# Sheet2.net
KiCad netlist of a schematic drawn in Altium Designer
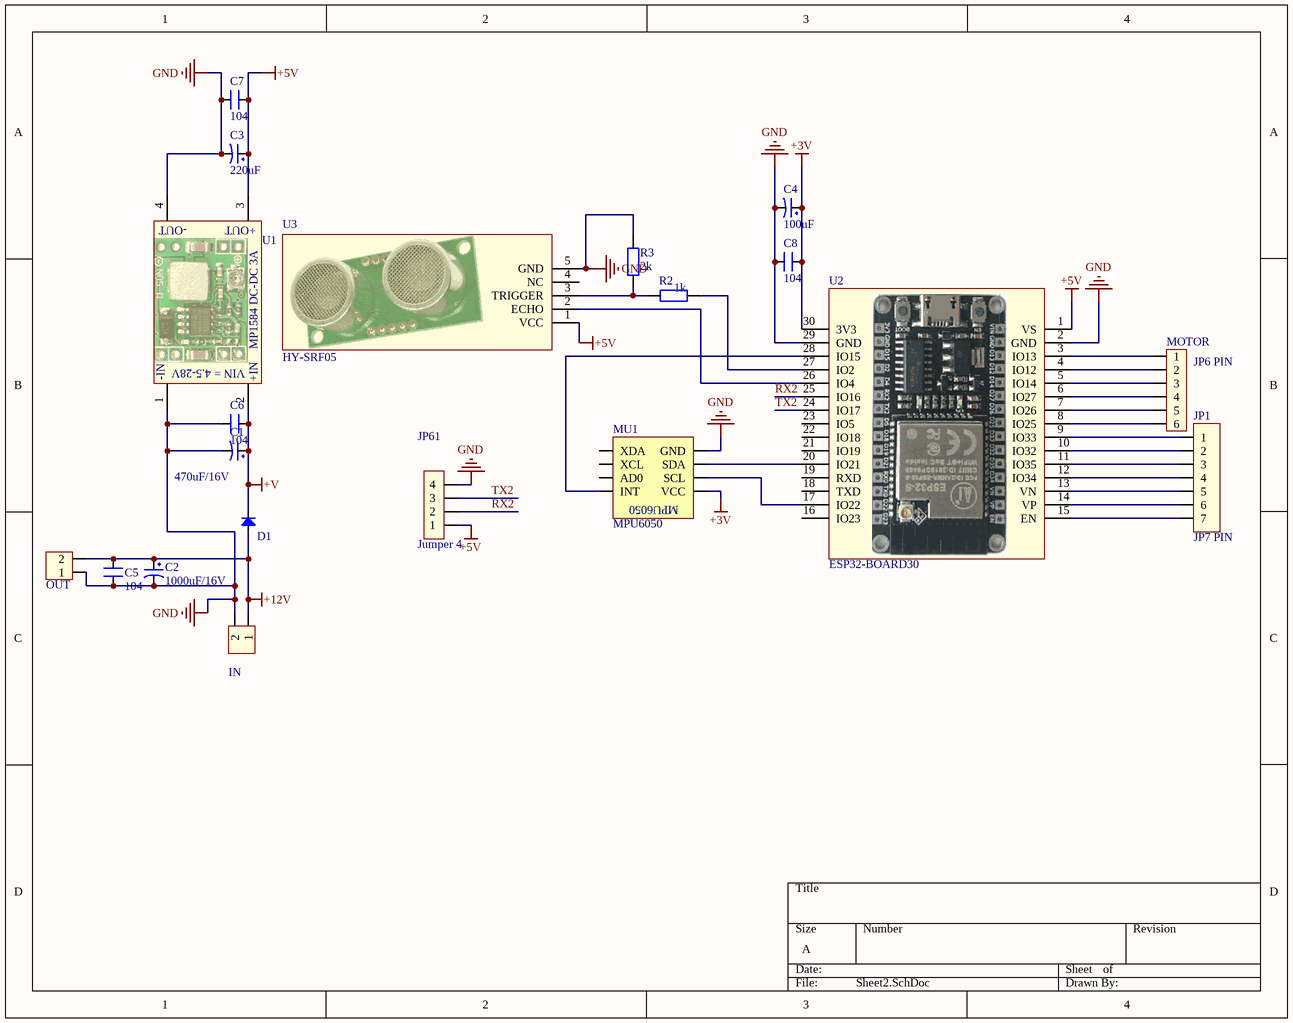
[diagram p0: Sheet2.SchDoc]

(export (version "E")
  (design (tool "Eeschema 10.0.6"))
  (components
    (comp (ref "C1")
      (value "470uF/16V")
      (footprint "CP1.5/3.4")
      (description "Cap 100uF/35V - 470uF/16V")
      (libsource (lib "PART_VDE") (part "CP3"))
    )
    (comp (ref "C2")
      (value "1000uF/16V")
      (footprint "CP1.5/3.4")
      (description "Cap 1000uF/16V - 220uF/50V")
      (libsource (lib "PART_VDE") (part "CP4"))
    )
    (comp (ref "C3")
      (value "220uF")
      (footprint "CP1/2.5")
      (description "C 47uF/50V , 220uF/16V")
      (libsource (lib "PART_VDE") (part "CP2"))
    )
    (comp (ref "C4")
      (value "100uF")
      (footprint "CP1/2")
      (description "Cap P  0,1uF < 22uF , 16 - 50V")
      (libsource (lib "PART_VDE") (part "CP1"))
    )
    (comp (ref "C5")
      (value "104")
      (footprint "CN1.5")
      (description "Cap np 104 => 105pF")
      (libsource (lib "PART_VDE") (part "CN2"))
    )
    (comp (ref "C6")
      (value "104")
      (footprint "CN1.5")
      (description "Cap np 104 => 105pF")
      (libsource (lib "PART_VDE") (part "CN2"))
    )
    (comp (ref "C7")
      (value "104")
      (footprint "CN1.5")
      (description "Cap np 104 => 105pF")
      (libsource (lib "PART_VDE") (part "CN2"))
    )
    (comp (ref "C8")
      (value "104")
      (footprint "CN2")
      (description "Cap np 104 => 105pF")
      (libsource (lib "PART_VDE") (part "CN2"))
    )
    (comp (ref "D1")
      (value "Diode")
      (footprint "D1A")
      (description "Default Diode")
      (fields (field (name "PUBLISHER") "Altium Limited"))
      (libsource (lib "Altium Library") (part "Diode"))
    )
    (comp (ref "IN")
      (value "Header 2")
      (footprint "KF301-2P")
      (description "Header 2 (Green)")
      (libsource (lib "") (part "Hed2_1"))
    )
    (comp (ref "JP1") (value "JP7 PIN") (footprint "JP7") (libsource (lib "PART_VDE") (part "JP7")))
    (comp (ref "JP61") (value "Jumper 4") (footprint "JP4") (libsource (lib "PART_VDE") (part "JP4")))
    (comp (ref "MOTOR")
      (value "JP6 PIN")
      (footprint "CON6")
      (description "ISP6 PIN")
      (libsource (lib "Altium Library") (part "ISP6"))
    )
    (comp (ref "MU1")
      (value "MPU6050")
      (footprint "MPU6050")
      (fields
        (field (name "MANUFACTURER") "Würth Elektronik eiSos GmbH")
        (field (name "PARTNO") "613004143121")
        (field (name "CREATED BY") "Karrer Zheng")
      )
      (libsource (lib "Altium Library") (part "MPU6050"))
    )
    (comp (ref "OUT")
      (value "Header 2")
      (footprint "KF301-2P")
      (description "Header 2 (Green)")
      (libsource (lib "PART_VDE") (part "Hed2"))
    )
    (comp (ref "R2")
      (value "1k")
      (footprint "R1/4W")
      (description "Resistor 1/4W")
      (libsource (lib "PART_VDE") (part "R1/4W"))
    )
    (comp (ref "R3")
      (value "2k")
      (footprint "R1/4W")
      (description "Resistor 1/4W")
      (libsource (lib "PART_VDE") (part "R1/4W"))
    )
    (comp (ref "U1")
      (value "Module MP1584 DC-DC")
      (footprint "MP1584 DC-DC")
      (libsource (lib "PART_VDE") (part "MP1584 DC-DC"))
    )
    (comp (ref "U2")
      (value "ESP32-BOARD30")
      (footprint "ESP32-BOARD30-900")
      (libsource (lib "PART_VDE") (part "ESP32-BOARD30"))
    )
    (comp (ref "U3") (value "HY-SRF05") (footprint "SRF05") (libsource (lib "PART_VDE") (part "HY-SRF05")))
  )
  (nets
    (net (code "1") (name "+3V") (class "Default")
      (node (ref "C4") (pin "1") (pinfunction "1_1") (pintype "passive"))
      (node (ref "C8") (pin "1") (pinfunction "1_1") (pintype "passive"))
      (node (ref "MU1") (pin "1") (pinfunction "VCC_1") (pintype "passive"))
      (node (ref "U2") (pin "30") (pinfunction "3V3_30") (pintype "passive"))
    )
    (net (code "2") (name "+5V") (class "Default")
      (node (ref "C3") (pin "1") (pinfunction "1_1") (pintype "passive"))
      (node (ref "C7") (pin "1") (pinfunction "1_1") (pintype "passive"))
      (node (ref "JP61") (pin "1") (pinfunction "1_1") (pintype "passive"))
      (node (ref "U1") (pin "3") (pinfunction "+OUT_3") (pintype "passive"))
      (node (ref "U2") (pin "1") (pinfunction "VS_1") (pintype "passive"))
      (node (ref "U3") (pin "1") (pinfunction "VCC_1") (pintype "passive"))
    )
    (net (code "3") (name "+12V") (class "Default")
      (node (ref "C2") (pin "1") (pinfunction "1_1") (pintype "passive"))
      (node (ref "C5") (pin "1") (pinfunction "1_1") (pintype "passive"))
      (node (ref "D1") (pin "1") (pinfunction "A_1") (pintype "passive"))
      (node (ref "IN") (pin "1") (pinfunction "1_1") (pintype "passive"))
      (node (ref "OUT") (pin "2") (pinfunction "2_2") (pintype "passive"))
    )
    (net (code "4") (name "+V") (class "Default")
      (node (ref "C1") (pin "1") (pinfunction "1_1") (pintype "passive"))
      (node (ref "C6") (pin "1") (pinfunction "1_1") (pintype "passive"))
      (node (ref "D1") (pin "2") (pinfunction "K_2") (pintype "passive"))
      (node (ref "U1") (pin "2") (pinfunction "+IN_2") (pintype "passive"))
    )
    (net (code "5") (name "/RX2") (class "Default")
      (node (ref "JP61") (pin "2") (pinfunction "2_2") (pintype "passive"))
      (node (ref "U2") (pin "25") (pinfunction "IO16_25") (pintype "passive"))
    )
    (net (code "6") (name "/TX2") (class "Default")
      (node (ref "JP61") (pin "3") (pinfunction "3_3") (pintype "passive"))
      (node (ref "U2") (pin "24") (pinfunction "IO17_24") (pintype "passive"))
    )
    (net (code "7") (name "GND") (class "Default")
      (node (ref "C1") (pin "2") (pinfunction "2_2") (pintype "passive"))
      (node (ref "C2") (pin "2") (pinfunction "2_2") (pintype "passive"))
      (node (ref "C3") (pin "2") (pinfunction "2_2") (pintype "passive"))
      (node (ref "C4") (pin "2") (pinfunction "2_2") (pintype "passive"))
      (node (ref "C5") (pin "2") (pinfunction "2_2") (pintype "passive"))
      (node (ref "C6") (pin "2") (pinfunction "2_2") (pintype "passive"))
      (node (ref "C7") (pin "2") (pinfunction "2_2") (pintype "passive"))
      (node (ref "C8") (pin "2") (pinfunction "2_2") (pintype "passive"))
      (node (ref "IN") (pin "2") (pinfunction "2_2") (pintype "passive"))
      (node (ref "JP61") (pin "4") (pinfunction "4_4") (pintype "passive"))
      (node (ref "MU1") (pin "2") (pinfunction "GND_2") (pintype "passive"))
      (node (ref "OUT") (pin "1") (pinfunction "1_1") (pintype "passive"))
      (node (ref "R3") (pin "2") (pinfunction "2_2") (pintype "passive"))
      (node (ref "U1") (pin "1") (pinfunction "-IN_1") (pintype "passive"))
      (node (ref "U1") (pin "4") (pinfunction "+OUT_4") (pintype "passive"))
      (node (ref "U2") (pin "2") (pinfunction "GND_2") (pintype "passive"))
      (node (ref "U2") (pin "29") (pinfunction "GND_29") (pintype "passive"))
      (node (ref "U3") (pin "5") (pinfunction "GND_5") (pintype "passive"))
    )
    (net (code "8") (name "Net-(MU1-INT)") (class "Default")
      (node (ref "MU1") (pin "8") (pinfunction "INT_8") (pintype "passive"))
      (node (ref "U2") (pin "28") (pinfunction "IO15_28") (pintype "passive"))
    )
    (net (code "9") (name "Net-(MU1-SCL)") (class "Default")
      (node (ref "MU1") (pin "3") (pinfunction "SCL_3") (pintype "passive"))
      (node (ref "U2") (pin "17") (pinfunction "IO22_17") (pintype "passive"))
    )
    (net (code "10") (name "Net-(MU1-SDA)") (class "Default")
      (node (ref "MU1") (pin "4") (pinfunction "SDA_4") (pintype "passive"))
      (node (ref "U2") (pin "20") (pinfunction "IO21_20") (pintype "passive"))
    )
    (net (code "11") (name "Net-(U2-EN)") (class "Default")
      (node (ref "JP1") (pin "7") (pinfunction "7_7") (pintype "passive"))
      (node (ref "U2") (pin "15") (pinfunction "EN_15") (pintype "passive"))
    )
    (net (code "12") (name "Net-(U2-IO2)") (class "Default")
      (node (ref "R2") (pin "1") (pinfunction "1_1") (pintype "passive"))
      (node (ref "U2") (pin "27") (pinfunction "IO2_27") (pintype "passive"))
    )
    (net (code "13") (name "Net-(U2-IO4)") (class "Default")
      (node (ref "U2") (pin "26") (pinfunction "IO4_26") (pintype "passive"))
      (node (ref "U3") (pin "2") (pinfunction "ECHO_2") (pintype "passive"))
    )
    (net (code "14") (name "Net-(U2-IO12)") (class "Default")
      (node (ref "MOTOR") (pin "2") (pinfunction "2_2") (pintype "passive"))
      (node (ref "U2") (pin "4") (pinfunction "IO12_4") (pintype "passive"))
    )
    (net (code "15") (name "Net-(U2-IO13)") (class "Default")
      (node (ref "MOTOR") (pin "1") (pinfunction "1_1") (pintype "passive"))
      (node (ref "U2") (pin "3") (pinfunction "IO13_3") (pintype "passive"))
    )
    (net (code "16") (name "Net-(U2-IO14)") (class "Default")
      (node (ref "MOTOR") (pin "3") (pinfunction "3_3") (pintype "passive"))
      (node (ref "U2") (pin "5") (pinfunction "IO14_5") (pintype "passive"))
    )
    (net (code "17") (name "Net-(U2-IO25)") (class "Default")
      (node (ref "MOTOR") (pin "6") (pinfunction "6_6") (pintype "passive"))
      (node (ref "U2") (pin "8") (pinfunction "IO25_8") (pintype "passive"))
    )
    (net (code "18") (name "Net-(U2-IO26)") (class "Default")
      (node (ref "MOTOR") (pin "5") (pinfunction "5_5") (pintype "passive"))
      (node (ref "U2") (pin "7") (pinfunction "IO26_7") (pintype "passive"))
    )
    (net (code "19") (name "Net-(U2-IO27)") (class "Default")
      (node (ref "MOTOR") (pin "4") (pinfunction "4_4") (pintype "passive"))
      (node (ref "U2") (pin "6") (pinfunction "IO27_6") (pintype "passive"))
    )
    (net (code "20") (name "Net-(U2-IO32)") (class "Default")
      (node (ref "JP1") (pin "2") (pinfunction "2_2") (pintype "passive"))
      (node (ref "U2") (pin "10") (pinfunction "IO32_10") (pintype "passive"))
    )
    (net (code "21") (name "Net-(U2-IO33)") (class "Default")
      (node (ref "JP1") (pin "1") (pinfunction "1_1") (pintype "passive"))
      (node (ref "U2") (pin "9") (pinfunction "IO33_9") (pintype "passive"))
    )
    (net (code "22") (name "Net-(U2-IO34)") (class "Default")
      (node (ref "JP1") (pin "4") (pinfunction "4_4") (pintype "passive"))
      (node (ref "U2") (pin "12") (pinfunction "IO34_12") (pintype "passive"))
    )
    (net (code "23") (name "Net-(U2-IO35)") (class "Default")
      (node (ref "JP1") (pin "3") (pinfunction "3_3") (pintype "passive"))
      (node (ref "U2") (pin "11") (pinfunction "IO35_11") (pintype "passive"))
    )
    (net (code "24") (name "Net-(U2-VN)") (class "Default")
      (node (ref "JP1") (pin "5") (pinfunction "5_5") (pintype "passive"))
      (node (ref "U2") (pin "13") (pinfunction "VN_13") (pintype "passive"))
    )
    (net (code "25") (name "Net-(U2-VP)") (class "Default")
      (node (ref "JP1") (pin "6") (pinfunction "6_6") (pintype "passive"))
      (node (ref "U2") (pin "14") (pinfunction "VP_14") (pintype "passive"))
    )
    (net (code "26") (name "Net-(U3-TRIGGER)") (class "Default")
      (node (ref "R2") (pin "2") (pinfunction "2_2") (pintype "passive"))
      (node (ref "R3") (pin "1") (pinfunction "1_1") (pintype "passive"))
      (node (ref "U3") (pin "3") (pinfunction "TRIGGER_3") (pintype "passive"))
    )
    (net (code "27") (name "unconnected-(MU1-AD0-Pad7)") (class "Default")
      (node (ref "MU1") (pin "7") (pinfunction "AD0_7") (pintype "passive"))
    )
    (net (code "28") (name "unconnected-(MU1-XCL-Pad6)") (class "Default")
      (node (ref "MU1") (pin "6") (pinfunction "XCL_6") (pintype "passive"))
    )
    (net (code "29") (name "unconnected-(MU1-XDA-Pad5)") (class "Default")
      (node (ref "MU1") (pin "5") (pinfunction "XDA_5") (pintype "passive"))
    )
    (net (code "30") (name "unconnected-(U2-IO5-Pad23)") (class "Default")
      (node (ref "U2") (pin "23") (pinfunction "IO5_23") (pintype "passive"))
    )
    (net (code "31") (name "unconnected-(U2-IO18-Pad22)") (class "Default")
      (node (ref "U2") (pin "22") (pinfunction "IO18_22") (pintype "passive"))
    )
    (net (code "32") (name "unconnected-(U2-IO19-Pad21)") (class "Default")
      (node (ref "U2") (pin "21") (pinfunction "IO19_21") (pintype "passive"))
    )
    (net (code "33") (name "unconnected-(U2-IO23-Pad16)") (class "Default")
      (node (ref "U2") (pin "16") (pinfunction "IO23_16") (pintype "passive"))
    )
    (net (code "34") (name "unconnected-(U2-RXD-Pad19)") (class "Default")
      (node (ref "U2") (pin "19") (pinfunction "RXD_19") (pintype "passive"))
    )
    (net (code "35") (name "unconnected-(U2-TXD-Pad18)") (class "Default")
      (node (ref "U2") (pin "18") (pinfunction "TXD_18") (pintype "passive"))
    )
    (net (code "36") (name "unconnected-(U3-NC-Pad4)") (class "Default")
      (node (ref "U3") (pin "4") (pinfunction "NC_4") (pintype "passive"))
    )
  )
)
